# TPIC8101DW.net
KiCad netlist of a schematic drawn in Altium Designer
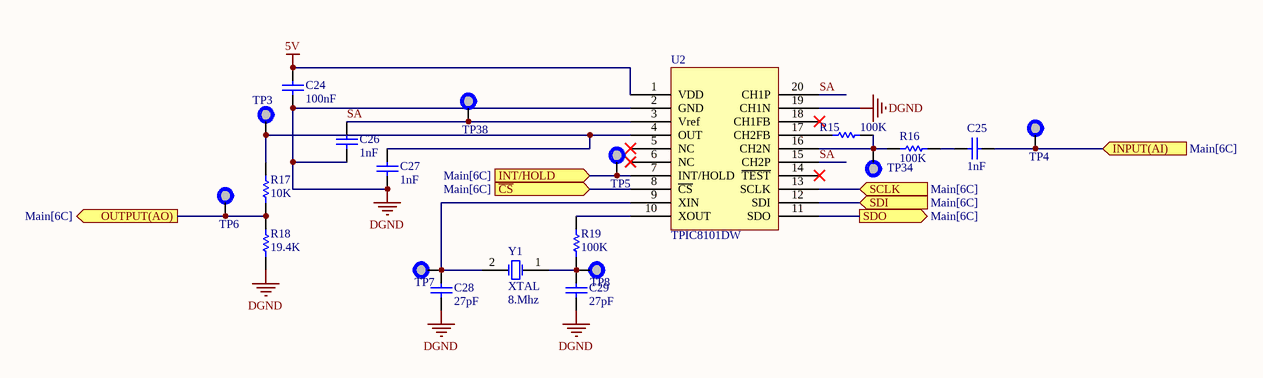
[diagram p0: TPIC8101DW.SchDoc]

(export (version "E")
  (design (tool "Eeschema 10.0.6"))
  (components
    (comp (ref "C24")
      (value "100nF")
      (footprint "0805C")
      (description "LOW ESR")
      (fields (field (name "PUBLISHER") "Altium Limited"))
      (libsource (lib "Miscellaneous Devices") (part "Cap"))
    )
    (comp (ref "C25")
      (value "1nF")
      (footprint "0805C")
      (description "LOW ESR")
      (fields (field (name "PUBLISHER") "Altium Limited"))
      (libsource (lib "Miscellaneous Devices") (part "Cap"))
    )
    (comp (ref "C26")
      (value "1nF")
      (footprint "0805C")
      (description "LOW ESR")
      (fields (field (name "PUBLISHER") "Altium Limited"))
      (libsource (lib "Miscellaneous Devices") (part "Cap"))
    )
    (comp (ref "C27")
      (value "1nF")
      (footprint "0805C")
      (description "LOW ESR")
      (fields (field (name "PUBLISHER") "Altium Limited"))
      (libsource (lib "Miscellaneous Devices") (part "Cap"))
    )
    (comp (ref "C28")
      (value "27pF")
      (footprint "0805C")
      (description "LOW ESR")
      (fields (field (name "Comment") "1nF") (field (name "PUBLISHER") "Altium Limited"))
      (libsource (lib "Miscellaneous Devices") (part "Cap"))
    )
    (comp (ref "C29")
      (value "27pF")
      (footprint "0805C")
      (description "LOW ESR")
      (fields (field (name "Comment") "1nF") (field (name "PUBLISHER") "Altium Limited"))
      (libsource (lib "Miscellaneous Devices") (part "Cap"))
    )
    (comp (ref "R15")
      (value "100K")
      (footprint "0805")
      (description "Resistor")
      (fields (field (name "Comment") "Res1") (field (name "PUBLISHER") "Altium Limited"))
      (libsource (lib "Miscellaneous Devices") (part "Res1"))
    )
    (comp (ref "R16")
      (value "100K")
      (footprint "0805")
      (description "Resistor")
      (fields (field (name "Comment") "Res1") (field (name "PUBLISHER") "Altium Limited"))
      (libsource (lib "Miscellaneous Devices") (part "Res1"))
    )
    (comp (ref "R17")
      (value "10K")
      (footprint "0805")
      (description "Resistor")
      (fields (field (name "Comment") "Res1") (field (name "PUBLISHER") "Altium Limited"))
      (libsource (lib "Miscellaneous Devices") (part "Res1"))
    )
    (comp (ref "R18")
      (value "19.4K")
      (footprint "0805")
      (description "Resistor")
      (fields (field (name "Comment") "Res1") (field (name "PUBLISHER") "Altium Limited"))
      (libsource (lib "Miscellaneous Devices") (part "Res1"))
    )
    (comp (ref "R19")
      (value "100K")
      (footprint "0805")
      (description "Resistor")
      (fields (field (name "Comment") "Res1") (field (name "PUBLISHER") "Altium Limited"))
      (libsource (lib "Miscellaneous Devices") (part "Res1"))
    )
    (comp (ref "TP3") (value "TestPoint") (footprint "TP") (libsource (lib "SchlibV0.1") (part "TestPoint")))
    (comp (ref "TP4") (value "TestPoint") (footprint "TP") (libsource (lib "SchlibV0.1") (part "TestPoint")))
    (comp (ref "TP5") (value "TestPoint") (footprint "TP") (libsource (lib "SchlibV0.1") (part "TestPoint")))
    (comp (ref "TP6") (value "TestPoint") (footprint "TP") (libsource (lib "SchlibV0.1") (part "TestPoint")))
    (comp (ref "TP7") (value "TestPoint") (footprint "TP") (libsource (lib "SchlibV0.1") (part "TestPoint")))
    (comp (ref "TP8") (value "TestPoint") (footprint "TP") (libsource (lib "SchlibV0.1") (part "TestPoint")))
    (comp (ref "TP34") (value "TestPoint") (footprint "TP") (libsource (lib "SchlibV0.1") (part "TestPoint")))
    (comp (ref "TP38") (value "TestPoint") (footprint "TP") (libsource (lib "SchlibV0.1") (part "TestPoint")))
    (comp (ref "U2")
      (value "TPIC8101DW")
      (footprint "SOIC-20")
      (description "Knock, SO20")
      (fields (field (name "MANUFACTURER") "TI"))
      (libsource (lib "Lib") (part "TPIC8101DW"))
    )
    (comp (ref "Y1")
      (value "XTAL")
      (footprint "XTAL")
      (description "Crystal Oscillator")
      (fields (field (name "ALTIUM_VALUE") "8.Mhz") (field (name "PUBLISHER") "Altium Limited"))
      (libsource (lib "Miscellaneous Devices") (part "XTAL"))
    )
  )
  (nets
    (net (code "1") (name "/INPUT(AI)") (class "Default")
      (node (ref "C25") (pin "1") (pinfunction "1_1") (pintype "passive"))
      (node (ref "TP4") (pin "1") (pintype "passive"))
    )
    (net (code "2") (name "/INT{slash}HOLD") (class "Default")
      (node (ref "TP5") (pin "1") (pintype "passive"))
      (node (ref "U2") (pin "7") (pinfunction "INT/HOLD_7") (pintype "passive"))
    )
    (net (code "3") (name "/OUTPUT(AO)") (class "Default")
      (node (ref "R17") (pin "1") (pinfunction "1_1") (pintype "passive"))
      (node (ref "R18") (pin "2") (pinfunction "2_2") (pintype "passive"))
      (node (ref "TP6") (pin "1") (pintype "passive"))
    )
    (net (code "4") (name "/SA") (class "Default")
      (node (ref "C26") (pin "2") (pinfunction "2_2") (pintype "passive"))
      (node (ref "TP38") (pin "1") (pintype "passive"))
      (node (ref "U2") (pin "15") (pinfunction "CH2P_15") (pintype "passive"))
      (node (ref "U2") (pin "20") (pinfunction "CH1P_20") (pintype "passive"))
      (node (ref "U2") (pin "3") (pinfunction "Vref_3") (pintype "passive"))
    )
    (net (code "5") (name "/SCLK") (class "Default")
      (node (ref "U2") (pin "13") (pinfunction "SCLK_13") (pintype "passive"))
    )
    (net (code "6") (name "/SDI") (class "Default")
      (node (ref "U2") (pin "12") (pinfunction "SDI_12") (pintype "passive"))
    )
    (net (code "7") (name "/SDO") (class "Default")
      (node (ref "U2") (pin "11") (pinfunction "SDO_11") (pintype "passive"))
    )
    (net (code "8") (name "/~{CS}") (class "Default")
      (node (ref "U2") (pin "8") (pinfunction "~{CS}_8") (pintype "passive"))
    )
    (net (code "9") (name "5V") (class "Default")
      (node (ref "C24") (pin "2") (pinfunction "2_2") (pintype "passive"))
      (node (ref "U2") (pin "1") (pinfunction "VDD_1") (pintype "passive"))
    )
    (net (code "10") (name "DGND") (class "Default")
      (node (ref "C24") (pin "1") (pinfunction "1_1") (pintype "passive"))
      (node (ref "C26") (pin "1") (pinfunction "1_1") (pintype "passive"))
      (node (ref "C27") (pin "1") (pinfunction "1_1") (pintype "passive"))
      (node (ref "C28") (pin "2") (pinfunction "2_2") (pintype "passive"))
      (node (ref "C29") (pin "2") (pinfunction "2_2") (pintype "passive"))
      (node (ref "R18") (pin "1") (pinfunction "1_1") (pintype "passive"))
      (node (ref "U2") (pin "19") (pinfunction "CH1N_19") (pintype "passive"))
      (node (ref "U2") (pin "2") (pinfunction "GND_2") (pintype "passive"))
    )
    (net (code "11") (name "Net-(C25-Pad2)") (class "Default")
      (node (ref "C25") (pin "2") (pinfunction "2_2") (pintype "passive"))
      (node (ref "R16") (pin "2") (pinfunction "2_2") (pintype "passive"))
    )
    (net (code "12") (name "Net-(U2-CH2FB)") (class "Default")
      (node (ref "R15") (pin "1") (pinfunction "1_1") (pintype "passive"))
      (node (ref "U2") (pin "17") (pinfunction "CH2FB_17") (pintype "passive"))
    )
    (net (code "13") (name "Net-(U2-CH2N)") (class "Default")
      (node (ref "R15") (pin "2") (pinfunction "2_2") (pintype "passive"))
      (node (ref "R16") (pin "1") (pinfunction "1_1") (pintype "passive"))
      (node (ref "TP34") (pin "1") (pintype "passive"))
      (node (ref "U2") (pin "16") (pinfunction "CH2N_16") (pintype "passive"))
    )
    (net (code "14") (name "Net-(U2-OUT)") (class "Default")
      (node (ref "C27") (pin "2") (pinfunction "2_2") (pintype "passive"))
      (node (ref "R17") (pin "2") (pinfunction "2_2") (pintype "passive"))
      (node (ref "TP3") (pin "1") (pintype "passive"))
      (node (ref "U2") (pin "4") (pinfunction "OUT_4") (pintype "passive"))
    )
    (net (code "15") (name "Net-(U2-XIN)") (class "Default")
      (node (ref "C28") (pin "1") (pinfunction "1_1") (pintype "passive"))
      (node (ref "TP7") (pin "1") (pintype "passive"))
      (node (ref "U2") (pin "9") (pinfunction "XIN_9") (pintype "passive"))
      (node (ref "Y1") (pin "2") (pinfunction "OSC2_2") (pintype "passive"))
    )
    (net (code "16") (name "Net-(U2-XOUT)") (class "Default")
      (node (ref "R19") (pin "2") (pinfunction "2_2") (pintype "passive"))
      (node (ref "U2") (pin "10") (pinfunction "XOUT_10") (pintype "passive"))
    )
    (net (code "17") (name "Net-(Y1-OSC1)") (class "Default")
      (node (ref "C29") (pin "1") (pinfunction "1_1") (pintype "passive"))
      (node (ref "R19") (pin "1") (pinfunction "1_1") (pintype "passive"))
      (node (ref "TP8") (pin "1") (pintype "passive"))
      (node (ref "Y1") (pin "1") (pinfunction "OSC1_1") (pintype "passive"))
    )
    (net (code "18") (name "unconnected-(U2-CH1FB-Pad18)") (class "Default")
      (node (ref "U2") (pin "18") (pinfunction "CH1FB_18") (pintype "passive+no_connect"))
    )
    (net (code "19") (name "unconnected-(U2-NC-Pad5)") (class "Default")
      (node (ref "U2") (pin "5") (pinfunction "NC_5") (pintype "passive+no_connect"))
    )
    (net (code "20") (name "unconnected-(U2-NC-Pad6)") (class "Default")
      (node (ref "U2") (pin "6") (pinfunction "NC_6") (pintype "passive+no_connect"))
    )
    (net (code "21") (name "unconnected-(U2-~{TEST}-Pad14)") (class "Default")
      (node (ref "U2") (pin "14") (pinfunction "~{TEST}_14") (pintype "passive+no_connect"))
    )
  )
)
